# v5_d.net
KiCad netlist of a schematic drawn in EasyEDA Pro
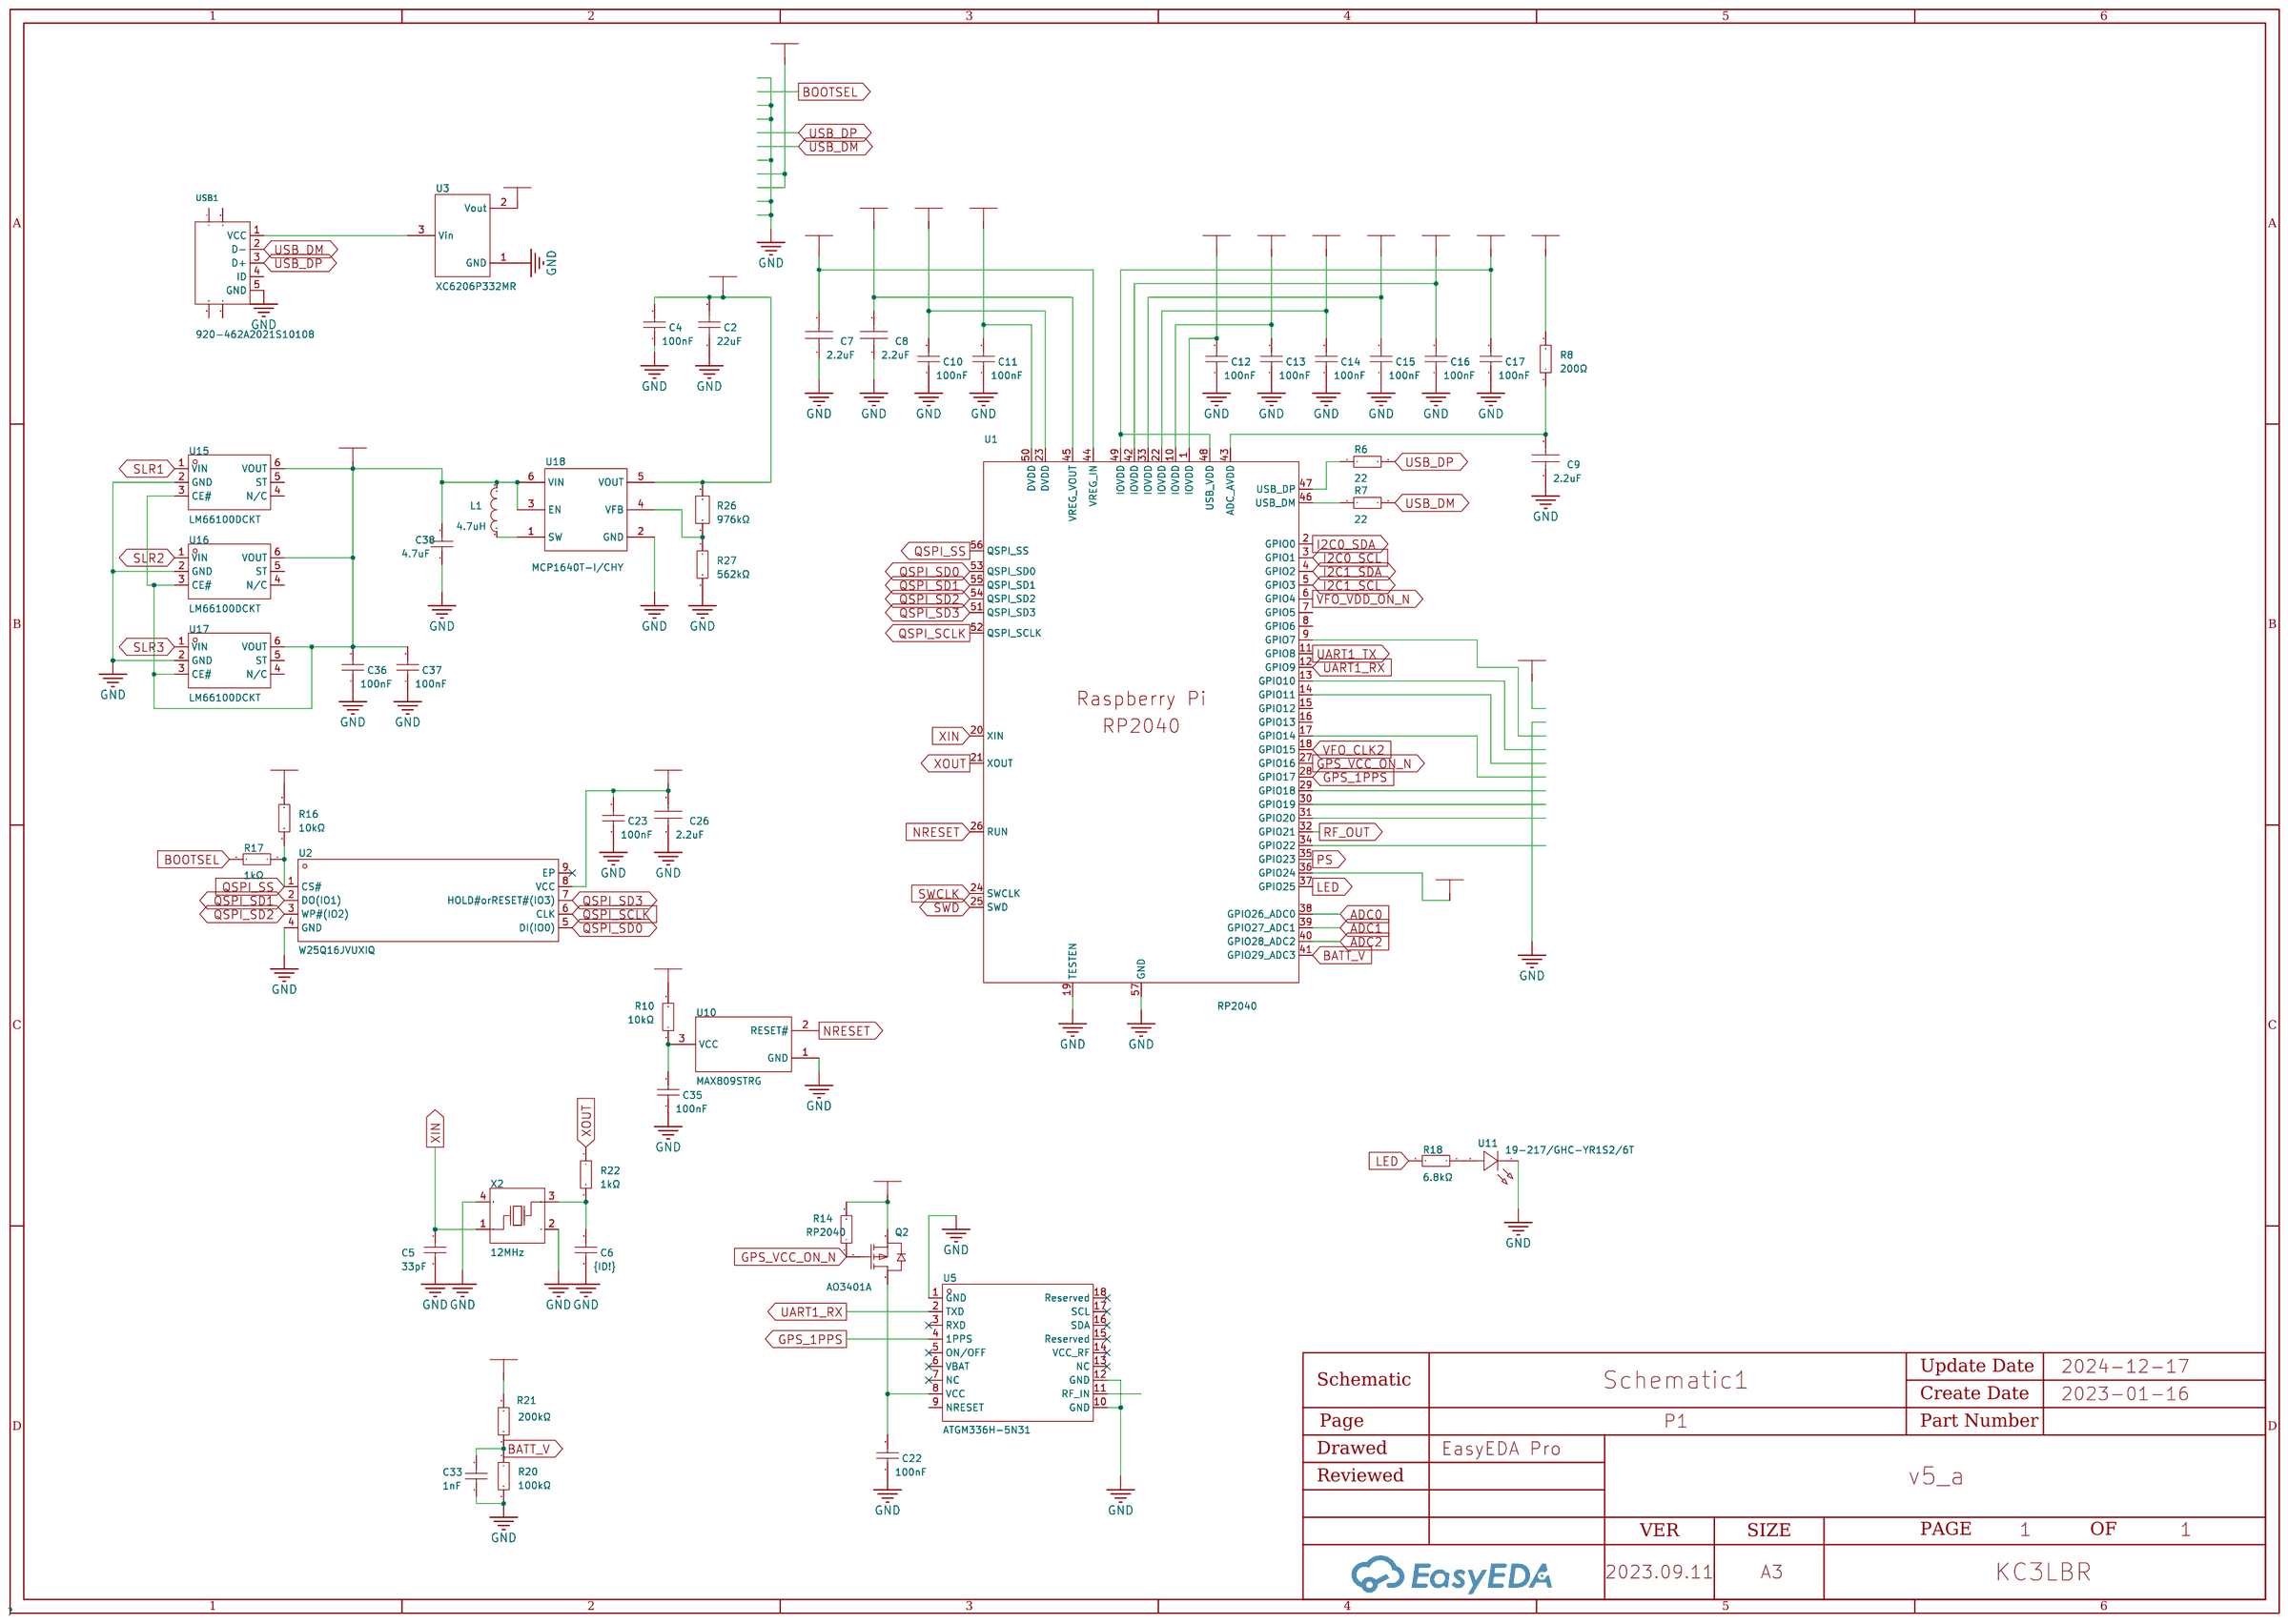
[diagram p0: schematic sheet]

(export (version "E")
  (design (tool "Eeschema 10.0.6"))
  (components
    (comp (ref "C2")
      (value "22uF")
      (footprint "easyedapro:C0603")
      (fields
        (field (name "Manufacturer Part") "CL10A226MQ8NRNC")
        (field (name "Manufacturer") "SAMSUNG(三星)")
      )
      (libsource (lib "easyedapro") (part "CL10A226MQ8NRNC"))
    )
    (comp (ref "C4")
      (value "100nF")
      (footprint "easyedapro:C0402_NEW")
      (fields
        (field (name "Manufacturer Part") "CL05B104KO5NNNC")
        (field (name "Manufacturer") "SAMSUNG(三星)")
      )
      (libsource (lib "easyedapro") (part "CL05B104KO5NNNC"))
    )
    (comp (ref "C5")
      (value "33pF")
      (footprint "easyedapro:C0402")
      (fields (field (name "Manufacturer Part") "0402CG330J500NT") (field (name "Manufacturer") "FH(风华)"))
      (libsource (lib "easyedapro") (part "0402CG330J500NT"))
    )
    (comp (ref "C6")
      (value "33pF")
      (footprint "easyedapro:C0402")
      (fields (field (name "Manufacturer Part") "0402CG330J500NT") (field (name "Manufacturer") "FH(风华)"))
      (libsource (lib "easyedapro") (part "0402CG330J500NT"))
    )
    (comp (ref "C7")
      (value "2.2uF")
      (footprint "easyedapro:C0402")
      (fields
        (field (name "Manufacturer Part") "CL05A225MQ5NSNC")
        (field (name "Manufacturer") "SAMSUNG(三星)")
      )
      (libsource (lib "easyedapro") (part "CL05A225MQ5NSNC"))
    )
    (comp (ref "C8")
      (value "2.2uF")
      (footprint "easyedapro:C0402")
      (fields
        (field (name "Manufacturer Part") "CL05A225MQ5NSNC")
        (field (name "Manufacturer") "SAMSUNG(三星)")
      )
      (libsource (lib "easyedapro") (part "CL05A225MQ5NSNC"))
    )
    (comp (ref "C9")
      (value "2.2uF")
      (footprint "easyedapro:C0402")
      (fields
        (field (name "Manufacturer Part") "CL05A225MQ5NSNC")
        (field (name "Manufacturer") "SAMSUNG(三星)")
      )
      (libsource (lib "easyedapro") (part "CL05A225MQ5NSNC"))
    )
    (comp (ref "C10")
      (value "100nF")
      (footprint "easyedapro:C0402_NEW")
      (fields
        (field (name "Manufacturer Part") "CL05B104KO5NNNC")
        (field (name "Manufacturer") "SAMSUNG(三星)")
      )
      (libsource (lib "easyedapro") (part "CL05B104KO5NNNC"))
    )
    (comp (ref "C11")
      (value "100nF")
      (footprint "easyedapro:C0402_NEW")
      (fields
        (field (name "Manufacturer Part") "CL05B104KO5NNNC")
        (field (name "Manufacturer") "SAMSUNG(三星)")
      )
      (libsource (lib "easyedapro") (part "CL05B104KO5NNNC"))
    )
    (comp (ref "C12")
      (value "100nF")
      (footprint "easyedapro:C0402_NEW")
      (fields
        (field (name "Manufacturer Part") "CL05B104KO5NNNC")
        (field (name "Manufacturer") "SAMSUNG(三星)")
      )
      (libsource (lib "easyedapro") (part "CL05B104KO5NNNC"))
    )
    (comp (ref "C13")
      (value "100nF")
      (footprint "easyedapro:C0402_NEW")
      (fields
        (field (name "Manufacturer Part") "CL05B104KO5NNNC")
        (field (name "Manufacturer") "SAMSUNG(三星)")
      )
      (libsource (lib "easyedapro") (part "CL05B104KO5NNNC"))
    )
    (comp (ref "C14")
      (value "100nF")
      (footprint "easyedapro:C0402_NEW")
      (fields
        (field (name "Manufacturer Part") "CL05B104KO5NNNC")
        (field (name "Manufacturer") "SAMSUNG(三星)")
      )
      (libsource (lib "easyedapro") (part "CL05B104KO5NNNC"))
    )
    (comp (ref "C15")
      (value "100nF")
      (footprint "easyedapro:C0402_NEW")
      (fields
        (field (name "Manufacturer Part") "CL05B104KO5NNNC")
        (field (name "Manufacturer") "SAMSUNG(三星)")
      )
      (libsource (lib "easyedapro") (part "CL05B104KO5NNNC"))
    )
    (comp (ref "C16")
      (value "100nF")
      (footprint "easyedapro:C0402_NEW")
      (fields
        (field (name "Manufacturer Part") "CL05B104KO5NNNC")
        (field (name "Manufacturer") "SAMSUNG(三星)")
      )
      (libsource (lib "easyedapro") (part "CL05B104KO5NNNC"))
    )
    (comp (ref "C17")
      (value "100nF")
      (footprint "easyedapro:C0402_NEW")
      (fields
        (field (name "Manufacturer Part") "CL05B104KO5NNNC")
        (field (name "Manufacturer") "SAMSUNG(三星)")
      )
      (libsource (lib "easyedapro") (part "CL05B104KO5NNNC"))
    )
    (comp (ref "C22")
      (value "100nF")
      (footprint "easyedapro:C0402_NEW")
      (fields
        (field (name "Manufacturer Part") "CL05B104KO5NNNC")
        (field (name "Manufacturer") "SAMSUNG(三星)")
      )
      (libsource (lib "easyedapro") (part "CL05B104KO5NNNC"))
    )
    (comp (ref "C23")
      (value "100nF")
      (footprint "easyedapro:C0402_NEW")
      (fields
        (field (name "Manufacturer Part") "CL05B104KO5NNNC")
        (field (name "Manufacturer") "SAMSUNG(三星)")
      )
      (libsource (lib "easyedapro") (part "CL05B104KO5NNNC"))
    )
    (comp (ref "C26")
      (value "2.2uF")
      (footprint "easyedapro:C0402")
      (fields
        (field (name "Manufacturer Part") "CL05A225MQ5NSNC")
        (field (name "Manufacturer") "SAMSUNG(三星)")
      )
      (libsource (lib "easyedapro") (part "CL05A225MQ5NSNC"))
    )
    (comp (ref "C33")
      (value "1nF")
      (footprint "easyedapro:C0402")
      (fields (field (name "Manufacturer Part") "0402B102K500NT") (field (name "Manufacturer") "FH(风华)"))
      (libsource (lib "easyedapro") (part "0402B102K500NT"))
    )
    (comp (ref "C35")
      (value "100nF")
      (footprint "easyedapro:C0402_NEW")
      (fields
        (field (name "Manufacturer Part") "CL05B104KO5NNNC")
        (field (name "Manufacturer") "SAMSUNG(三星)")
      )
      (libsource (lib "easyedapro") (part "CL05B104KO5NNNC"))
    )
    (comp (ref "C36")
      (value "100nF")
      (footprint "easyedapro:C0402_NEW")
      (fields
        (field (name "Manufacturer Part") "CL05B104KO5NNNC")
        (field (name "Manufacturer") "SAMSUNG(三星)")
      )
      (libsource (lib "easyedapro") (part "CL05B104KO5NNNC"))
    )
    (comp (ref "C37")
      (value "100nF")
      (footprint "easyedapro:C0402_NEW")
      (fields
        (field (name "Manufacturer Part") "CL05B104KO5NNNC")
        (field (name "Manufacturer") "SAMSUNG(三星)")
      )
      (libsource (lib "easyedapro") (part "CL05B104KO5NNNC"))
    )
    (comp (ref "C38")
      (value "4.7uF")
      (footprint "easyedapro:C0603")
      (fields
        (field (name "Manufacturer Part") "CL10A475KO8NNNC")
        (field (name "Manufacturer") "SAMSUNG(三星)")
      )
      (libsource (lib "easyedapro") (part "CL10A475KO8NNNC"))
    )
    (comp (ref "L1")
      (value "4.7uH")
      (footprint "easyedapro:IND-SMD_L2.5-W1.8")
      (fields
        (field (name "Manufacturer Part") "CBC2518T4R7M")
        (field (name "Manufacturer") "TAIYO YUDEN(太诱)")
      )
      (libsource (lib "easyedapro") (part "CBC2518T4R7M"))
    )
    (comp (ref "Q2")
      (value "AO3401A")
      (footprint "easyedapro:SOT-23_L2.9-W1.3-P1.90-LS2.4-BR")
      (fields (field (name "Manufacturer") "AOS"))
      (libsource (lib "easyedapro") (part "AO3401A"))
    )
    (comp (ref "R6")
      (value "22")
      (footprint "easyedapro:R0402")
      (fields
        (field (name "Manufacturer Part") "0402WGF220JTCE")
        (field (name "Manufacturer") "UNI-ROYAL(厚声)")
      )
      (libsource (lib "easyedapro") (part "0402WGF220JTCE"))
    )
    (comp (ref "R7")
      (value "22")
      (footprint "easyedapro:R0402")
      (fields
        (field (name "Manufacturer Part") "0402WGF220JTCE")
        (field (name "Manufacturer") "UNI-ROYAL(厚声)")
      )
      (libsource (lib "easyedapro") (part "0402WGF220JTCE"))
    )
    (comp (ref "R8")
      (value "200Ω")
      (footprint "easyedapro:R0402")
      (fields
        (field (name "Manufacturer Part") "0402WGF2000TCE")
        (field (name "Manufacturer") "UNI-ROYAL(厚声)")
      )
      (libsource (lib "easyedapro") (part "0402WGF2000TCE"))
    )
    (comp (ref "R10")
      (value "10kΩ")
      (footprint "easyedapro:R0402")
      (fields
        (field (name "Manufacturer Part") "0402WGF1002TCE")
        (field (name "Manufacturer") "UNI-ROYAL(厚声)")
      )
      (libsource (lib "easyedapro") (part "0402WGF1002TCE"))
    )
    (comp (ref "R14")
      (value "RP2040")
      (footprint "easyedapro:R0402")
      (fields (field (name "Manufacturer") "Raspberry Pi(树莓派)"))
      (libsource (lib "easyedapro") (part "0402WGF1002TCE"))
    )
    (comp (ref "R16")
      (value "10kΩ")
      (footprint "easyedapro:R0402")
      (fields
        (field (name "Manufacturer Part") "0402WGF1002TCE")
        (field (name "Manufacturer") "UNI-ROYAL(厚声)")
      )
      (libsource (lib "easyedapro") (part "0402WGF1002TCE"))
    )
    (comp (ref "R17")
      (value "1kΩ")
      (footprint "easyedapro:R0402")
      (fields
        (field (name "Manufacturer Part") "0402WGF1001TCE")
        (field (name "Manufacturer") "UNI-ROYAL(厚声)")
      )
      (libsource (lib "easyedapro") (part "0402WGF1001TCE"))
    )
    (comp (ref "R18")
      (value "6.8kΩ")
      (footprint "easyedapro:R0402")
      (fields
        (field (name "Manufacturer Part") "0402WGF6801TCE")
        (field (name "Manufacturer") "UNI-ROYAL(厚声)")
      )
      (libsource (lib "easyedapro") (part "0402WGF6801TCE"))
    )
    (comp (ref "R20")
      (value "100kΩ")
      (footprint "easyedapro:R0402")
      (fields
        (field (name "Manufacturer Part") "0402WGF1003TCE")
        (field (name "Manufacturer") "UNI-ROYAL(厚声)")
      )
      (libsource (lib "easyedapro") (part "0402WGF1003TCE"))
    )
    (comp (ref "R21")
      (value "200kΩ")
      (footprint "easyedapro:R0402")
      (fields
        (field (name "Manufacturer Part") "0402WGF2003TCE")
        (field (name "Manufacturer") "UNI-ROYAL(厚声)")
      )
      (libsource (lib "easyedapro") (part "0402WGF2003TCE"))
    )
    (comp (ref "R22")
      (value "1kΩ")
      (footprint "easyedapro:R0402")
      (fields
        (field (name "Manufacturer Part") "0402WGF1001TCE")
        (field (name "Manufacturer") "UNI-ROYAL(厚声)")
      )
      (libsource (lib "easyedapro") (part "0402WGF1001TCE"))
    )
    (comp (ref "R26")
      (value "976kΩ")
      (footprint "easyedapro:R0402")
      (fields (field (name "Manufacturer Part") "RC0402FR-07976KL") (field (name "Manufacturer") "YAGEO(国巨)"))
      (libsource (lib "easyedapro") (part "RC0402FR-07976KL"))
    )
    (comp (ref "R27")
      (value "562kΩ")
      (footprint "easyedapro:R0402")
      (fields (field (name "Manufacturer Part") "RC0402FR-07562KL") (field (name "Manufacturer") "YAGEO(国巨)"))
      (libsource (lib "easyedapro") (part "RC0402FR-07562KL"))
    )
    (comp (ref "U1")
      (value "RP2040")
      (footprint "easyedapro:LQFN-56_L7.0-W7.0-P0.4-EP")
      (fields (field (name "Manufacturer") "Raspberry Pi(树莓派)"))
      (libsource (lib "easyedapro") (part "RP2040"))
    )
    (comp (ref "U2")
      (value "W25Q16JVUXIQ")
      (footprint "easyedapro:USON-8_L3.0-W2.0-P0.50-BL-EP")
      (fields (field (name "Manufacturer") "WINBOND(华邦)"))
      (libsource (lib "easyedapro") (part "W25Q16JVUXIQ"))
    )
    (comp (ref "U3")
      (value "XC6206P332MR")
      (footprint "easyedapro:SOT-23-3_L2.9-W1.6-P1.90-LS2.8-BR")
      (fields (field (name "Manufacturer") "GOODWORK(固得沃克)"))
      (libsource (lib "easyedapro") (part "XC6206P332MR"))
    )
    (comp (ref "U5")
      (value "ATGM336H-5N31")
      (footprint "easyedapro:GPSM-SMD_ATGM336H-TR")
      (fields (field (name "Manufacturer") "杭州中科微"))
      (libsource (lib "easyedapro") (part "ATGM336H-5N31"))
    )
    (comp (ref "U10")
      (value "MAX809STRG")
      (footprint "easyedapro:SOT-23-3_L2.9-W1.6-P1.90-LS2.8-BR")
      (fields (field (name "Manufacturer") "onsemi(安森美)"))
      (libsource (lib "easyedapro") (part "MAX809STRG"))
    )
    (comp (ref "U11")
      (value "19-217/GHC-YR1S2/6T")
      (footprint "easyedapro:LED0603-RD_GREEN")
      (fields (field (name "Manufacturer") "EVERLIGHT(亿光)"))
      (libsource (lib "easyedapro") (part "19-217/GHC-YR1S2/6T"))
    )
    (comp (ref "U15")
      (value "LM66100DCKT")
      (footprint "easyedapro:SC-70-6_L2.0-W1.3-P0.65-LS2.1-BL")
      (fields (field (name "Manufacturer") "TI(德州仪器)"))
      (libsource (lib "easyedapro") (part "LM66100DCKT"))
    )
    (comp (ref "U16")
      (value "LM66100DCKT")
      (footprint "easyedapro:SC-70-6_L2.0-W1.3-P0.65-LS2.1-BL")
      (fields (field (name "Manufacturer") "TI(德州仪器)"))
      (libsource (lib "easyedapro") (part "LM66100DCKT"))
    )
    (comp (ref "U17")
      (value "LM66100DCKT")
      (footprint "easyedapro:SC-70-6_L2.0-W1.3-P0.65-LS2.1-BL")
      (fields (field (name "Manufacturer") "TI(德州仪器)"))
      (libsource (lib "easyedapro") (part "LM66100DCKT"))
    )
    (comp (ref "U18")
      (value "MCP1640T-I/CHY")
      (footprint "easyedapro:SOT-23-6_L2.9-W1.6-P0.95-LS2.8-BR")
      (fields (field (name "Manufacturer") "MICROCHIP(美国微芯)"))
      (libsource (lib "easyedapro") (part "MCP1640T-I/CHY"))
    )
    (comp (ref "USB1")
      (value "920-462A2021S10108")
      (footprint "easyedapro:MINI-USB-SMD_C105424")
      (description "Connector Type:Mini-B Standard:USB 2.0 Gender:Female Number of Ports:1 Number of Contacts:5P")
      (fields (field (name "Manufacturer") "精拓金"))
      (libsource (lib "easyedapro") (part "USB-MINI-SMD-9.2X9.4-H3.7"))
    )
    (comp (ref "X2")
      (value "12MHz")
      (footprint "easyedapro:OSC-SMD_4P-L3.2-W2.5-BL")
      (fields (field (name "Manufacturer Part") "X322512MSB4SI") (field (name "Manufacturer") "YXC(扬兴晶振)"))
      (libsource (lib "easyedapro") (part "X322512MSB4SI"))
    )
  )
  (nets
    (net (code "1") (name "1V1") (class "Default")
      (node (ref "C10") (pin "2") (pinfunction "2_2") (pintype "input"))
      (node (ref "C11") (pin "2") (pinfunction "2_2") (pintype "input"))
      (node (ref "C8") (pin "2") (pinfunction "2_2") (pintype "input"))
      (node (ref "U1") (pin "23") (pinfunction "DVDD_23") (pintype "bidirectional"))
      (node (ref "U1") (pin "45") (pinfunction "VREG_VOUT_45") (pintype "bidirectional"))
      (node (ref "U1") (pin "50") (pinfunction "DVDD_50") (pintype "bidirectional"))
    )
    (net (code "2") (name "3V3") (class "Default")
      (node (ref "C12") (pin "2") (pinfunction "2_2") (pintype "input"))
      (node (ref "C13") (pin "2") (pinfunction "2_2") (pintype "input"))
      (node (ref "C14") (pin "2") (pinfunction "2_2") (pintype "input"))
      (node (ref "C15") (pin "2") (pinfunction "2_2") (pintype "input"))
      (node (ref "C16") (pin "2") (pinfunction "2_2") (pintype "input"))
      (node (ref "C17") (pin "2") (pinfunction "2_2") (pintype "input"))
      (node (ref "C2") (pin "2") (pinfunction "2_2") (pintype "input"))
      (node (ref "C23") (pin "2") (pinfunction "2_2") (pintype "input"))
      (node (ref "C26") (pin "2") (pinfunction "2_2") (pintype "input"))
      (node (ref "C4") (pin "2") (pinfunction "2_2") (pintype "input"))
      (node (ref "C7") (pin "2") (pinfunction "2_2") (pintype "input"))
      (node (ref "Q2") (pin "2") (pinfunction "S_2") (pintype "input"))
      (node (ref "R10") (pin "2") (pinfunction "2_2") (pintype "input"))
      (node (ref "R14") (pin "2") (pinfunction "2_2") (pintype "input"))
      (node (ref "R16") (pin "2") (pinfunction "2_2") (pintype "input"))
      (node (ref "R26") (pin "2") (pinfunction "2_2") (pintype "unspecified"))
      (node (ref "R8") (pin "2") (pinfunction "2_2") (pintype "input"))
      (node (ref "U1") (pin "1") (pinfunction "IOVDD_1") (pintype "bidirectional"))
      (node (ref "U1") (pin "10") (pinfunction "IOVDD_10") (pintype "bidirectional"))
      (node (ref "U1") (pin "22") (pinfunction "IOVDD_22") (pintype "bidirectional"))
      (node (ref "U1") (pin "33") (pinfunction "IOVDD_33") (pintype "bidirectional"))
      (node (ref "U1") (pin "36") (pinfunction "GPIO24_36") (pintype "bidirectional"))
      (node (ref "U1") (pin "42") (pinfunction "IOVDD_42") (pintype "bidirectional"))
      (node (ref "U1") (pin "44") (pinfunction "VREG_IN_44") (pintype "bidirectional"))
      (node (ref "U1") (pin "48") (pinfunction "USB_VDD_48") (pintype "bidirectional"))
      (node (ref "U1") (pin "49") (pinfunction "IOVDD_49") (pintype "bidirectional"))
      (node (ref "U18") (pin "5") (pinfunction "VOUT_5") (pintype "input"))
      (node (ref "U2") (pin "8") (pinfunction "VCC_8") (pintype "input"))
      (node (ref "U3") (pin "2") (pinfunction "Vout_2") (pintype "input"))
    )
    (net (code "3") (name "ADC0") (class "Default")
      (node (ref "U1") (pin "38") (pinfunction "GPIO26_ADC0_38") (pintype "bidirectional"))
    )
    (net (code "4") (name "ADC1") (class "Default")
      (node (ref "U1") (pin "39") (pinfunction "GPIO27_ADC1_39") (pintype "bidirectional"))
    )
    (net (code "5") (name "ADC2") (class "Default")
      (node (ref "U1") (pin "40") (pinfunction "GPIO28_ADC2_40") (pintype "bidirectional"))
    )
    (net (code "6") (name "BATT_V") (class "Default")
      (node (ref "C33") (pin "2") (pinfunction "2_2") (pintype "input"))
      (node (ref "R20") (pin "1") (pinfunction "1_1") (pintype "input"))
      (node (ref "R21") (pin "1") (pinfunction "1_1") (pintype "input"))
      (node (ref "U1") (pin "41") (pinfunction "GPIO29_ADC3_41") (pintype "bidirectional"))
    )
    (net (code "7") (name "BOOTSEL") (class "Default")
      (node (ref "R17") (pin "2") (pinfunction "2_2") (pintype "input"))
    )
    (net (code "8") (name "GND") (class "Default")
      (node (ref "C10") (pin "1") (pinfunction "1_1") (pintype "input"))
      (node (ref "C11") (pin "1") (pinfunction "1_1") (pintype "input"))
      (node (ref "C12") (pin "1") (pinfunction "1_1") (pintype "input"))
      (node (ref "C13") (pin "1") (pinfunction "1_1") (pintype "input"))
      (node (ref "C14") (pin "1") (pinfunction "1_1") (pintype "input"))
      (node (ref "C15") (pin "1") (pinfunction "1_1") (pintype "input"))
      (node (ref "C16") (pin "1") (pinfunction "1_1") (pintype "input"))
      (node (ref "C17") (pin "1") (pinfunction "1_1") (pintype "input"))
      (node (ref "C2") (pin "1") (pinfunction "1_1") (pintype "input"))
      (node (ref "C22") (pin "1") (pinfunction "1_1") (pintype "input"))
      (node (ref "C23") (pin "1") (pinfunction "1_1") (pintype "input"))
      (node (ref "C26") (pin "1") (pinfunction "1_1") (pintype "input"))
      (node (ref "C33") (pin "1") (pinfunction "1_1") (pintype "input"))
      (node (ref "C35") (pin "1") (pinfunction "1_1") (pintype "input"))
      (node (ref "C36") (pin "1") (pinfunction "1_1") (pintype "input"))
      (node (ref "C37") (pin "1") (pinfunction "1_1") (pintype "input"))
      (node (ref "C38") (pin "1") (pinfunction "1_1") (pintype "input"))
      (node (ref "C4") (pin "1") (pinfunction "1_1") (pintype "input"))
      (node (ref "C5") (pin "1") (pinfunction "1_1") (pintype "input"))
      (node (ref "C6") (pin "1") (pinfunction "1_1") (pintype "input"))
      (node (ref "C7") (pin "1") (pinfunction "1_1") (pintype "input"))
      (node (ref "C8") (pin "1") (pinfunction "1_1") (pintype "input"))
      (node (ref "C9") (pin "1") (pinfunction "1_1") (pintype "input"))
      (node (ref "R20") (pin "2") (pinfunction "2_2") (pintype "input"))
      (node (ref "R27") (pin "1") (pinfunction "1_1") (pintype "unspecified"))
      (node (ref "U1") (pin "19") (pinfunction "TESTEN_19") (pintype "input"))
      (node (ref "U1") (pin "57") (pinfunction "GND_57") (pintype "bidirectional"))
      (node (ref "U10") (pin "1") (pinfunction "GND_1") (pintype "input"))
      (node (ref "U11") (pin "1") (pinfunction "K_1") (pintype "unspecified"))
      (node (ref "U15") (pin "2") (pinfunction "GND_2") (pintype "input"))
      (node (ref "U16") (pin "2") (pinfunction "GND_2") (pintype "input"))
      (node (ref "U17") (pin "2") (pinfunction "GND_2") (pintype "input"))
      (node (ref "U18") (pin "2") (pinfunction "GND_2") (pintype "input"))
      (node (ref "U2") (pin "4") (pinfunction "GND_4") (pintype "input"))
      (node (ref "U3") (pin "1") (pinfunction "GND_1") (pintype "input"))
      (node (ref "U5") (pin "1") (pinfunction "GND_1") (pintype "input"))
      (node (ref "U5") (pin "10") (pinfunction "GND_10") (pintype "input"))
      (node (ref "U5") (pin "12") (pinfunction "GND_12") (pintype "input"))
      (node (ref "USB1") (pin "5") (pinfunction "GND_5") (pintype "input"))
      (node (ref "X2") (pin "2") (pinfunction "GND_2") (pintype "input"))
      (node (ref "X2") (pin "4") (pinfunction "GND_4") (pintype "input"))
    )
    (net (code "9") (name "GPS_1PPS") (class "Default")
      (node (ref "U1") (pin "28") (pinfunction "GPIO17_28") (pintype "bidirectional"))
      (node (ref "U5") (pin "4") (pinfunction "1PPS_4") (pintype "input"))
    )
    (net (code "10") (name "GPS_VCC_ON_N") (class "Default")
      (node (ref "Q2") (pin "1") (pinfunction "G_1") (pintype "input"))
      (node (ref "R14") (pin "1") (pinfunction "1_1") (pintype "input"))
      (node (ref "U1") (pin "27") (pinfunction "GPIO16_27") (pintype "bidirectional"))
    )
    (net (code "11") (name "I2C0_SCL") (class "Default")
      (node (ref "U1") (pin "3") (pinfunction "GPIO1_3") (pintype "bidirectional"))
    )
    (net (code "12") (name "I2C0_SDA") (class "Default")
      (node (ref "U1") (pin "2") (pinfunction "GPIO0_2") (pintype "bidirectional"))
    )
    (net (code "13") (name "I2C1_SCL") (class "Default")
      (node (ref "U1") (pin "5") (pinfunction "GPIO3_5") (pintype "bidirectional"))
    )
    (net (code "14") (name "I2C1_SDA") (class "Default")
      (node (ref "U1") (pin "4") (pinfunction "GPIO2_4") (pintype "bidirectional"))
    )
    (net (code "15") (name "LED") (class "Default")
      (node (ref "R18") (pin "2") (pinfunction "2_2") (pintype "input"))
      (node (ref "U1") (pin "37") (pinfunction "GPIO25_37") (pintype "bidirectional"))
    )
    (net (code "16") (name "NRESET") (class "Default")
      (node (ref "U1") (pin "26") (pinfunction "RUN_26") (pintype "input"))
      (node (ref "U10") (pin "2") (pinfunction "RESET#_2") (pintype "input"))
    )
    (net (code "17") (name "Net-(Q2-D)") (class "Default")
      (node (ref "C22") (pin "2") (pinfunction "2_2") (pintype "input"))
      (node (ref "Q2") (pin "3") (pinfunction "D_3") (pintype "input"))
      (node (ref "U5") (pin "8") (pinfunction "VCC_8") (pintype "input"))
    )
    (net (code "18") (name "Net-(U1-ADC_AVDD)") (class "Default")
      (node (ref "C9") (pin "2") (pinfunction "2_2") (pintype "input"))
      (node (ref "R8") (pin "1") (pinfunction "1_1") (pintype "input"))
      (node (ref "U1") (pin "43") (pinfunction "ADC_AVDD_43") (pintype "bidirectional"))
    )
    (net (code "19") (name "Net-(U1-USB_DM)") (class "Default")
      (node (ref "R7") (pin "1") (pinfunction "1_1") (pintype "input"))
      (node (ref "U1") (pin "46") (pinfunction "USB_DM_46") (pintype "bidirectional"))
    )
    (net (code "20") (name "Net-(U1-USB_DP)") (class "Default")
      (node (ref "R6") (pin "1") (pinfunction "1_1") (pintype "input"))
      (node (ref "U1") (pin "47") (pinfunction "USB_DP_47") (pintype "bidirectional"))
    )
    (net (code "21") (name "Net-(U3-Vin)") (class "Default")
      (node (ref "U3") (pin "3") (pinfunction "Vin_3") (pintype "input"))
      (node (ref "USB1") (pin "1") (pinfunction "VCC_1") (pintype "input"))
    )
    (net (code "22") (name "Net-(U10-VCC)") (class "Default")
      (node (ref "C35") (pin "2") (pinfunction "2_2") (pintype "input"))
      (node (ref "R10") (pin "1") (pinfunction "1_1") (pintype "input"))
      (node (ref "U10") (pin "3") (pinfunction "VCC_3") (pintype "input"))
    )
    (net (code "23") (name "Net-(U11-A)") (class "Default")
      (node (ref "R18") (pin "1") (pinfunction "1_1") (pintype "input"))
      (node (ref "U11") (pin "2") (pinfunction "A_2") (pintype "unspecified"))
    )
    (net (code "24") (name "Net-(U18-SW)") (class "Default")
      (node (ref "L1") (pin "1") (pinfunction "1_1") (pintype "input"))
      (node (ref "U18") (pin "1") (pinfunction "SW_1") (pintype "input"))
    )
    (net (code "25") (name "Net-(U18-VFB)") (class "Default")
      (node (ref "R26") (pin "1") (pinfunction "1_1") (pintype "unspecified"))
      (node (ref "R27") (pin "2") (pinfunction "2_2") (pintype "unspecified"))
      (node (ref "U18") (pin "4") (pinfunction "VFB_4") (pintype "input"))
    )
    (net (code "26") (name "Net-(X2-OSC2)") (class "Default")
      (node (ref "C6") (pin "2") (pinfunction "2_2") (pintype "input"))
      (node (ref "R22") (pin "2") (pinfunction "2_2") (pintype "input"))
      (node (ref "X2") (pin "3") (pinfunction "OSC2_3") (pintype "input"))
    )
    (net (code "27") (name "PS") (class "Default")
      (node (ref "U1") (pin "35") (pinfunction "GPIO23_35") (pintype "bidirectional"))
    )
    (net (code "28") (name "QSPI_SCLK") (class "Default")
      (node (ref "U1") (pin "52") (pinfunction "QSPI_SCLK_52") (pintype "output"))
      (node (ref "U2") (pin "6") (pinfunction "CLK_6") (pintype "input"))
    )
    (net (code "29") (name "QSPI_SD0") (class "Default")
      (node (ref "U1") (pin "53") (pinfunction "QSPI_SD0_53") (pintype "bidirectional"))
      (node (ref "U2") (pin "5") (pinfunction "DI(IO0)_5") (pintype "input"))
    )
    (net (code "30") (name "QSPI_SD1") (class "Default")
      (node (ref "U1") (pin "55") (pinfunction "QSPI_SD1_55") (pintype "bidirectional"))
      (node (ref "U2") (pin "2") (pinfunction "DO(IO1)_2") (pintype "input"))
    )
    (net (code "31") (name "QSPI_SD2") (class "Default")
      (node (ref "U1") (pin "54") (pinfunction "QSPI_SD2_54") (pintype "bidirectional"))
      (node (ref "U2") (pin "3") (pinfunction "WP#(IO2)_3") (pintype "input"))
    )
    (net (code "32") (name "QSPI_SD3") (class "Default")
      (node (ref "U1") (pin "51") (pinfunction "QSPI_SD3_51") (pintype "bidirectional"))
      (node (ref "U2") (pin "7") (pinfunction "HOLD#orRESET#(IO3)_7") (pintype "input"))
    )
    (net (code "33") (name "QSPI_SS") (class "Default")
      (node (ref "R16") (pin "1") (pinfunction "1_1") (pintype "input"))
      (node (ref "R17") (pin "1") (pinfunction "1_1") (pintype "input"))
      (node (ref "U1") (pin "56") (pinfunction "QSPI_SS_56") (pintype "bidirectional"))
      (node (ref "U2") (pin "1") (pinfunction "CS#_1") (pintype "input"))
    )
    (net (code "34") (name "RF_OUT") (class "Default")
      (node (ref "U1") (pin "32") (pinfunction "GPIO21_32") (pintype "bidirectional"))
    )
    (net (code "35") (name "SLR1") (class "Default")
      (node (ref "U15") (pin "1") (pinfunction "VIN_1") (pintype "input"))
    )
    (net (code "36") (name "SLR2") (class "Default")
      (node (ref "U16") (pin "1") (pinfunction "VIN_1") (pintype "input"))
    )
    (net (code "37") (name "SLR3") (class "Default")
      (node (ref "U17") (pin "1") (pinfunction "VIN_1") (pintype "input"))
    )
    (net (code "38") (name "SWCLK") (class "Default")
      (node (ref "U1") (pin "24") (pinfunction "SWCLK_24") (pintype "output"))
    )
    (net (code "39") (name "SWD") (class "Default")
      (node (ref "U1") (pin "25") (pinfunction "SWD_25") (pintype "bidirectional"))
    )
    (net (code "40") (name "UART1_RX") (class "Default")
      (node (ref "U1") (pin "12") (pinfunction "GPIO9_12") (pintype "bidirectional"))
      (node (ref "U5") (pin "2") (pinfunction "TXD_2") (pintype "input"))
    )
    (net (code "41") (name "UART1_TX") (class "Default")
      (node (ref "U1") (pin "11") (pinfunction "GPIO8_11") (pintype "bidirectional"))
    )
    (net (code "42") (name "USB_DM") (class "Default")
      (node (ref "R7") (pin "2") (pinfunction "2_2") (pintype "input"))
      (node (ref "USB1") (pin "2") (pinfunction "D-_2") (pintype "input"))
    )
    (net (code "43") (name "USB_DP") (class "Default")
      (node (ref "R6") (pin "2") (pinfunction "2_2") (pintype "input"))
      (node (ref "USB1") (pin "3") (pinfunction "D+_3") (pintype "input"))
    )
    (net (code "44") (name "VBUS") (class "Default")
      (node (ref "C36") (pin "2") (pinfunction "2_2") (pintype "input"))
      (node (ref "C37") (pin "2") (pinfunction "2_2") (pintype "input"))
      (node (ref "C38") (pin "2") (pinfunction "2_2") (pintype "input"))
      (node (ref "L1") (pin "2") (pinfunction "2_2") (pintype "input"))
      (node (ref "R21") (pin "2") (pinfunction "2_2") (pintype "input"))
      (node (ref "U15") (pin "3") (pinfunction "CE#_3") (pintype "input"))
      (node (ref "U15") (pin "6") (pinfunction "VOUT_6") (pintype "input"))
      (node (ref "U16") (pin "3") (pinfunction "CE#_3") (pintype "input"))
      (node (ref "U16") (pin "6") (pinfunction "VOUT_6") (pintype "input"))
      (node (ref "U17") (pin "3") (pinfunction "CE#_3") (pintype "input"))
      (node (ref "U17") (pin "6") (pinfunction "VOUT_6") (pintype "input"))
      (node (ref "U18") (pin "3") (pinfunction "EN_3") (pintype "input"))
      (node (ref "U18") (pin "6") (pinfunction "VIN_6") (pintype "input"))
    )
    (net (code "45") (name "VFO_CLK2") (class "Default")
      (node (ref "U1") (pin "18") (pinfunction "GPIO15_18") (pintype "bidirectional"))
    )
    (net (code "46") (name "VFO_VDD_ON_N") (class "Default")
      (node (ref "U1") (pin "6") (pinfunction "GPIO4_6") (pintype "bidirectional"))
    )
    (net (code "47") (name "XIN") (class "Default")
      (node (ref "C5") (pin "2") (pinfunction "2_2") (pintype "input"))
      (node (ref "U1") (pin "20") (pinfunction "XIN_20") (pintype "input"))
      (node (ref "X2") (pin "1") (pinfunction "OSC1_1") (pintype "input"))
    )
    (net (code "48") (name "XOUT") (class "Default")
      (node (ref "R22") (pin "1") (pinfunction "1_1") (pintype "input"))
      (node (ref "U1") (pin "21") (pinfunction "XOUT_21") (pintype "input"))
    )
    (net (code "49") (name "unconnected-(U1-GPIO5-Pad7)") (class "Default")
      (node (ref "U1") (pin "7") (pinfunction "GPIO5_7") (pintype "bidirectional"))
    )
    (net (code "50") (name "unconnected-(U1-GPIO6-Pad8)") (class "Default")
      (node (ref "U1") (pin "8") (pinfunction "GPIO6_8") (pintype "bidirectional"))
    )
    (net (code "51") (name "unconnected-(U1-GPIO7-Pad9)") (class "Default")
      (node (ref "U1") (pin "9") (pinfunction "GPIO7_9") (pintype "bidirectional"))
    )
    (net (code "52") (name "unconnected-(U1-GPIO10-Pad13)") (class "Default")
      (node (ref "U1") (pin "13") (pinfunction "GPIO10_13") (pintype "bidirectional"))
    )
    (net (code "53") (name "unconnected-(U1-GPIO11-Pad14)") (class "Default")
      (node (ref "U1") (pin "14") (pinfunction "GPIO11_14") (pintype "bidirectional"))
    )
    (net (code "54") (name "unconnected-(U1-GPIO12-Pad15)") (class "Default")
      (node (ref "U1") (pin "15") (pinfunction "GPIO12_15") (pintype "bidirectional"))
    )
    (net (code "55") (name "unconnected-(U1-GPIO13-Pad16)") (class "Default")
      (node (ref "U1") (pin "16") (pinfunction "GPIO13_16") (pintype "bidirectional"))
    )
    (net (code "56") (name "unconnected-(U1-GPIO14-Pad17)") (class "Default")
      (node (ref "U1") (pin "17") (pinfunction "GPIO14_17") (pintype "bidirectional"))
    )
    (net (code "57") (name "unconnected-(U1-GPIO18-Pad29)") (class "Default")
      (node (ref "U1") (pin "29") (pinfunction "GPIO18_29") (pintype "bidirectional"))
    )
    (net (code "58") (name "unconnected-(U1-GPIO19-Pad30)") (class "Default")
      (node (ref "U1") (pin "30") (pinfunction "GPIO19_30") (pintype "bidirectional"))
    )
    (net (code "59") (name "unconnected-(U1-GPIO20-Pad31)") (class "Default")
      (node (ref "U1") (pin "31") (pinfunction "GPIO20_31") (pintype "bidirectional"))
    )
    (net (code "60") (name "unconnected-(U1-GPIO22-Pad34)") (class "Default")
      (node (ref "U1") (pin "34") (pinfunction "GPIO22_34") (pintype "bidirectional"))
    )
    (net (code "61") (name "unconnected-(U2-EP-Pad9)") (class "Default")
      (node (ref "U2") (pin "9") (pinfunction "EP_9") (pintype "input+no_connect"))
    )
    (net (code "62") (name "unconnected-(U5-NC-Pad7)") (class "Default")
      (node (ref "U5") (pin "7") (pinfunction "NC_7") (pintype "input+no_connect"))
    )
    (net (code "63") (name "unconnected-(U5-NC-Pad13)") (class "Default")
      (node (ref "U5") (pin "13") (pinfunction "NC_13") (pintype "input+no_connect"))
    )
    (net (code "64") (name "unconnected-(U5-NRESET-Pad9)") (class "Default")
      (node (ref "U5") (pin "9") (pinfunction "NRESET_9") (pintype "input"))
    )
    (net (code "65") (name "unconnected-(U5-ON{slash}OFF-Pad5)") (class "Default")
      (node (ref "U5") (pin "5") (pinfunction "ON/OFF_5") (pintype "input+no_connect"))
    )
    (net (code "66") (name "unconnected-(U5-RF_IN-Pad11)") (class "Default")
      (node (ref "U5") (pin "11") (pinfunction "RF_IN_11") (pintype "input"))
    )
    (net (code "67") (name "unconnected-(U5-RXD-Pad3)") (class "Default")
      (node (ref "U5") (pin "3") (pinfunction "RXD_3") (pintype "input+no_connect"))
    )
    (net (code "68") (name "unconnected-(U5-Reserved-Pad15)") (class "Default")
      (node (ref "U5") (pin "15") (pinfunction "Reserved_15") (pintype "input+no_connect"))
    )
    (net (code "69") (name "unconnected-(U5-Reserved-Pad18)") (class "Default")
      (node (ref "U5") (pin "18") (pinfunction "Reserved_18") (pintype "input+no_connect"))
    )
    (net (code "70") (name "unconnected-(U5-SCL-Pad17)") (class "Default")
      (node (ref "U5") (pin "17") (pinfunction "SCL_17") (pintype "input+no_connect"))
    )
    (net (code "71") (name "unconnected-(U5-SDA-Pad16)") (class "Default")
      (node (ref "U5") (pin "16") (pinfunction "SDA_16") (pintype "input+no_connect"))
    )
    (net (code "72") (name "unconnected-(U5-VBAT-Pad6)") (class "Default")
      (node (ref "U5") (pin "6") (pinfunction "VBAT_6") (pintype "input+no_connect"))
    )
    (net (code "73") (name "unconnected-(U5-VCC_RF-Pad14)") (class "Default")
      (node (ref "U5") (pin "14") (pinfunction "VCC_RF_14") (pintype "input+no_connect"))
    )
    (net (code "74") (name "unconnected-(U15-N{slash}C-Pad4)") (class "Default")
      (node (ref "U15") (pin "4") (pinfunction "N/C_4") (pintype "input"))
    )
    (net (code "75") (name "unconnected-(U15-ST-Pad5)") (class "Default")
      (node (ref "U15") (pin "5") (pinfunction "ST_5") (pintype "input"))
    )
    (net (code "76") (name "unconnected-(U16-N{slash}C-Pad4)") (class "Default")
      (node (ref "U16") (pin "4") (pinfunction "N/C_4") (pintype "input"))
    )
    (net (code "77") (name "unconnected-(U16-ST-Pad5)") (class "Default")
      (node (ref "U16") (pin "5") (pinfunction "ST_5") (pintype "input"))
    )
    (net (code "78") (name "unconnected-(U17-N{slash}C-Pad4)") (class "Default")
      (node (ref "U17") (pin "4") (pinfunction "N/C_4") (pintype "input"))
    )
    (net (code "79") (name "unconnected-(U17-ST-Pad5)") (class "Default")
      (node (ref "U17") (pin "5") (pinfunction "ST_5") (pintype "input"))
    )
    (net (code "80") (name "unconnected-(USB1-ID-Pad4)") (class "Default")
      (node (ref "USB1") (pin "4") (pinfunction "ID_4") (pintype "input"))
    )
    (net (code "81") (name "unconnected-(USB1-Pad6)") (class "Default")
      (node (ref "USB1") (pin "6") (pinfunction "6_6") (pintype "input"))
    )
    (net (code "82") (name "unconnected-(USB1-Pad7)") (class "Default")
      (node (ref "USB1") (pin "7") (pinfunction "7_7") (pintype "input"))
    )
    (net (code "83") (name "unconnected-(USB1-Pad8)") (class "Default")
      (node (ref "USB1") (pin "8") (pinfunction "8_8") (pintype "input"))
    )
    (net (code "84") (name "unconnected-(USB1-Pad9)") (class "Default")
      (node (ref "USB1") (pin "9") (pinfunction "9_9") (pintype "input"))
    )
  )
)
